# cs3.net
KiCad netlist of a schematic drawn in EAGLE
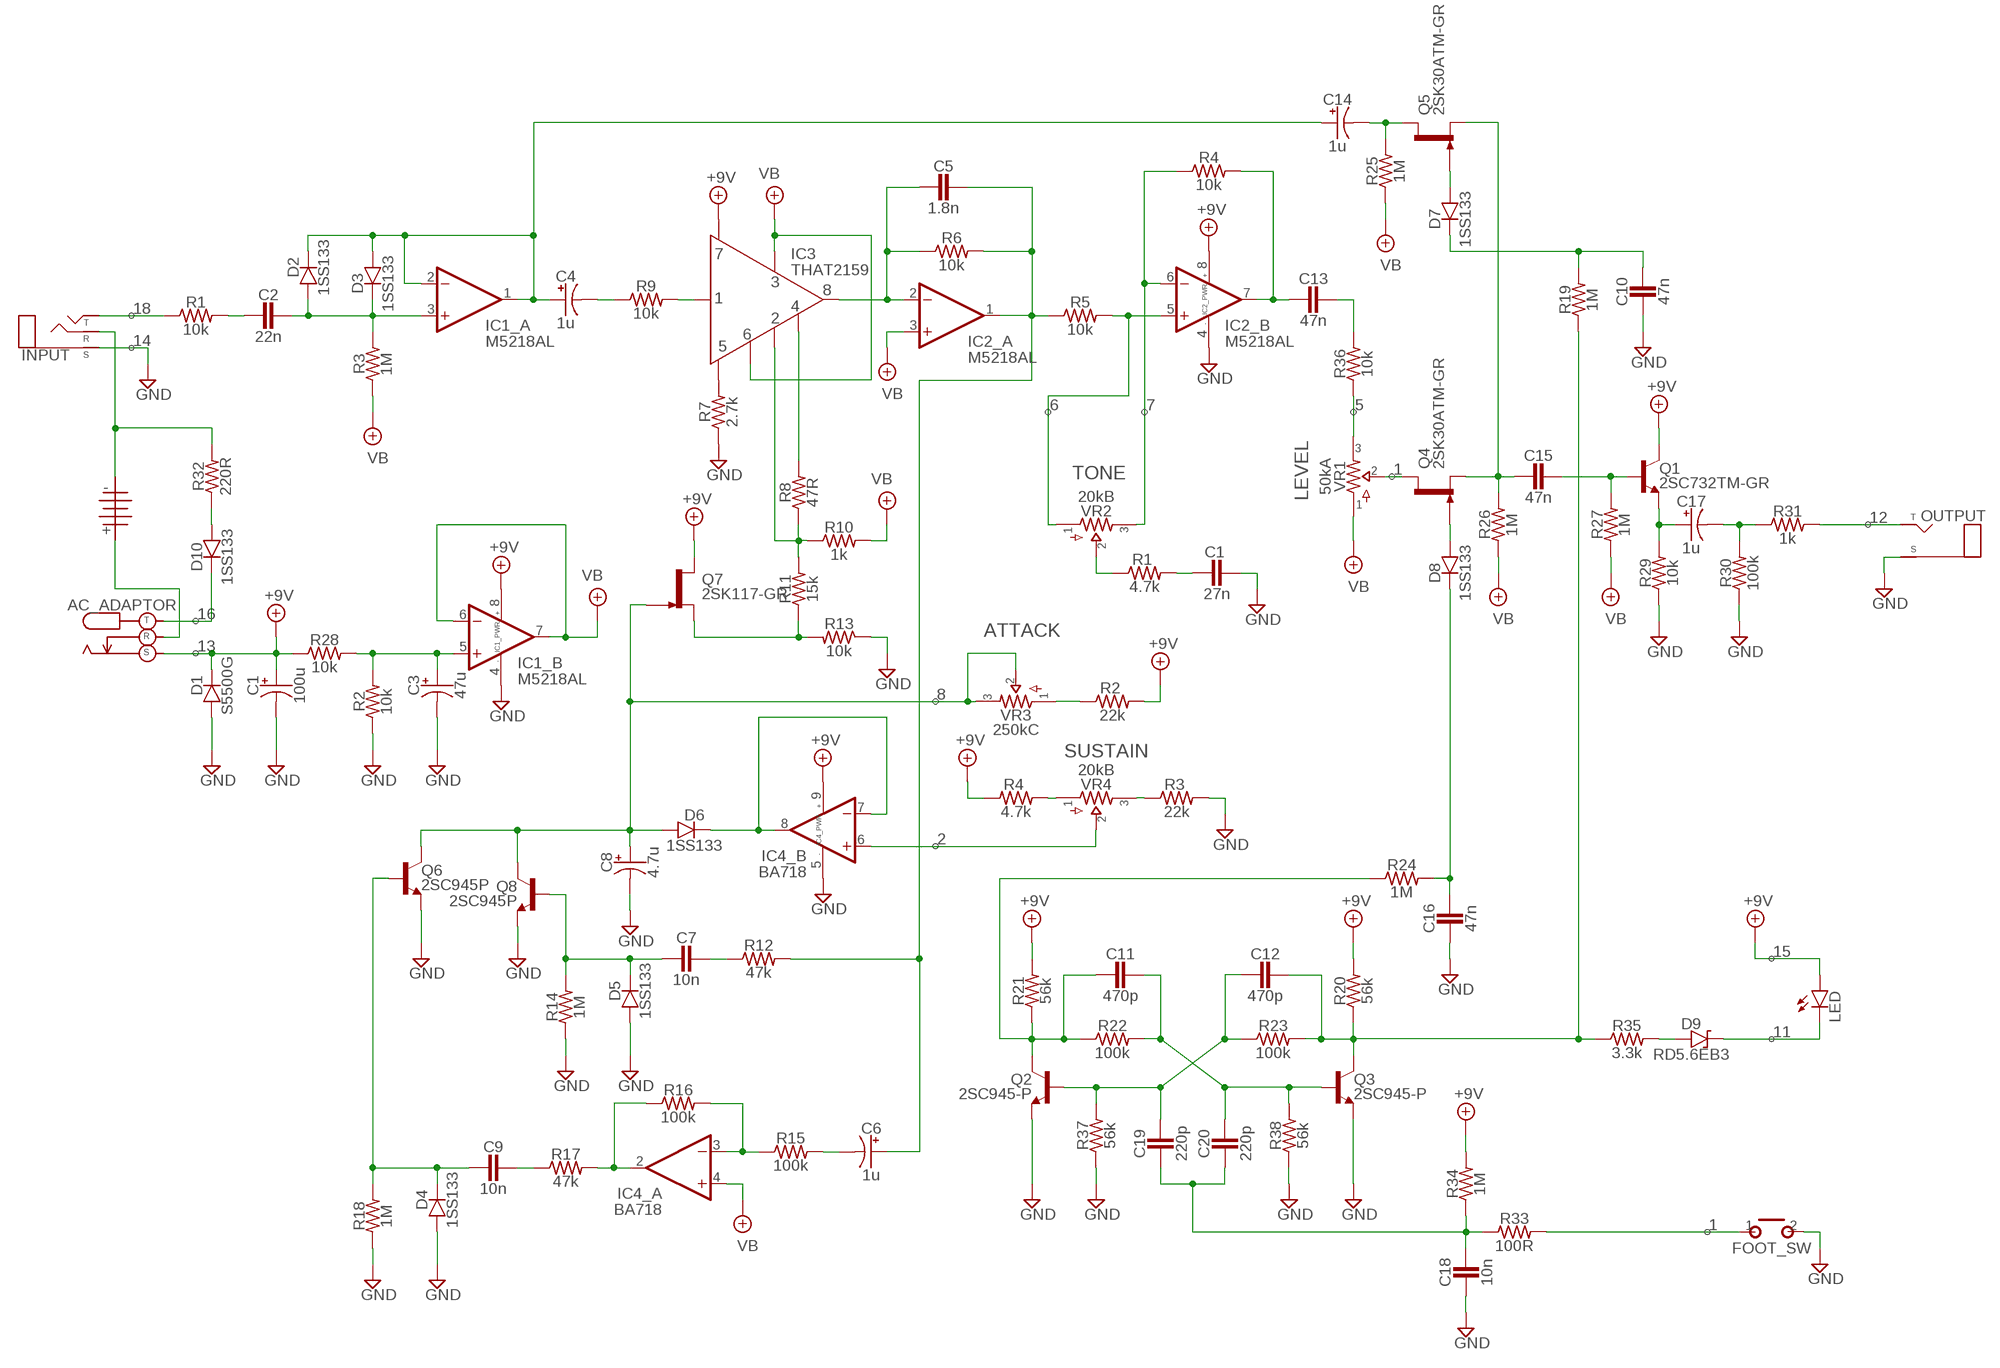
[diagram p0: schematic, sheet 1]

(export (version "E")
  (design (tool "Eeschema 10.0.6"))
  (components
    (comp (ref "1101")
      (value "BATTERY")
      (footprint "eagle-import:TWO_PADS")
      (libsource (lib "eagle-import") (part "BATTERY"))
    )
    (comp (ref "AC_ADAPTOR")
      (value "DC_KOBICONN")
      (footprint "eagle-import:DC_KOBICONN")
      (libsource (lib "eagle-import") (part "DC_KOBICONN"))
    )
    (comp (ref "C1")
      (value "100u")
      (footprint "eagle-import:040_020")
      (libsource (lib "eagle-import") (part "0400"))
    )
    (comp (ref "C1 ")
      (value "27n")
      (footprint "eagle-import:BOX_SMALL")
      (libsource (lib "eagle-import") (part "CER/FILMBOX.1"))
    )
    (comp (ref "C2")
      (value "22n")
      (footprint "eagle-import:BOX_SMALL")
      (libsource (lib "eagle-import") (part "CER/FILMBOX.1"))
    )
    (comp (ref "C3")
      (value "47u")
      (footprint "eagle-import:040_020")
      (libsource (lib "eagle-import") (part "0400"))
    )
    (comp (ref "C4")
      (value "1u")
      (footprint "eagle-import:040_020")
      (libsource (lib "eagle-import") (part "0400"))
    )
    (comp (ref "C5")
      (value "1.8n")
      (footprint "eagle-import:BOX_SMALL")
      (libsource (lib "eagle-import") (part "CER/FILMBOX.1"))
    )
    (comp (ref "C6")
      (value "1u")
      (footprint "eagle-import:040_020")
      (libsource (lib "eagle-import") (part "0400"))
    )
    (comp (ref "C7")
      (value "10n")
      (footprint "eagle-import:BOX_SMALL")
      (libsource (lib "eagle-import") (part "CER/FILMBOX.1"))
    )
    (comp (ref "C8")
      (value "4.7u")
      (footprint "eagle-import:040_020")
      (libsource (lib "eagle-import") (part "0400"))
    )
    (comp (ref "C9")
      (value "10n")
      (footprint "eagle-import:BOX_SMALL")
      (libsource (lib "eagle-import") (part "CER/FILMBOX.1"))
    )
    (comp (ref "C10")
      (value "47n")
      (footprint "eagle-import:BOX_SMALL")
      (libsource (lib "eagle-import") (part "CER/FILMBOX.1"))
    )
    (comp (ref "C11")
      (value "470p")
      (footprint "eagle-import:BOX_SMALL")
      (libsource (lib "eagle-import") (part "CER/FILMBOX.1"))
    )
    (comp (ref "C12")
      (value "470p")
      (footprint "eagle-import:BOX_SMALL")
      (libsource (lib "eagle-import") (part "CER/FILMBOX.1"))
    )
    (comp (ref "C13")
      (value "47n")
      (footprint "eagle-import:BOX_SMALL")
      (libsource (lib "eagle-import") (part "CER/FILMBOX.1"))
    )
    (comp (ref "C14")
      (value "1u")
      (footprint "eagle-import:040_020")
      (libsource (lib "eagle-import") (part "0400"))
    )
    (comp (ref "C15")
      (value "47n")
      (footprint "eagle-import:BOX_SMALL")
      (libsource (lib "eagle-import") (part "CER/FILMBOX.1"))
    )
    (comp (ref "C16")
      (value "47n")
      (footprint "eagle-import:BOX_SMALL")
      (libsource (lib "eagle-import") (part "CER/FILMBOX.1"))
    )
    (comp (ref "C17")
      (value "1u")
      (footprint "eagle-import:040_020")
      (libsource (lib "eagle-import") (part "0400"))
    )
    (comp (ref "C18")
      (value "10n")
      (footprint "eagle-import:BOX_SMALL")
      (libsource (lib "eagle-import") (part "CER/FILMBOX.1"))
    )
    (comp (ref "C19")
      (value "220p")
      (footprint "eagle-import:BOX_SMALL")
      (libsource (lib "eagle-import") (part "CER/FILMBOX.1"))
    )
    (comp (ref "C20")
      (value "220p")
      (footprint "eagle-import:BOX_SMALL")
      (libsource (lib "eagle-import") (part "CER/FILMBOX.1"))
    )
    (comp (ref "D1")
      (value "S5500G")
      (footprint "eagle-import:DO35-2")
      (libsource (lib "eagle-import") (part "DO35.2"))
    )
    (comp (ref "D2")
      (value "1SS133")
      (footprint "eagle-import:DO35-2")
      (libsource (lib "eagle-import") (part "DO35.2"))
    )
    (comp (ref "D3")
      (value "1SS133")
      (footprint "eagle-import:DO35-2")
      (libsource (lib "eagle-import") (part "DO35.2"))
    )
    (comp (ref "D4")
      (value "1SS133")
      (footprint "eagle-import:DO35-2")
      (libsource (lib "eagle-import") (part "DO35.2"))
    )
    (comp (ref "D5")
      (value "1SS133")
      (footprint "eagle-import:DO35-2")
      (libsource (lib "eagle-import") (part "DO35.2"))
    )
    (comp (ref "D6")
      (value "1SS133")
      (footprint "eagle-import:DO35-2")
      (libsource (lib "eagle-import") (part "DO35.2"))
    )
    (comp (ref "D7")
      (value "1SS133")
      (footprint "eagle-import:DO35-2")
      (libsource (lib "eagle-import") (part "DO35.2"))
    )
    (comp (ref "D8")
      (value "1SS133")
      (footprint "eagle-import:DO35-2")
      (libsource (lib "eagle-import") (part "DO35.2"))
    )
    (comp (ref "D9")
      (value "RD5.6EB3")
      (footprint "eagle-import:DO41-2")
      (libsource (lib "eagle-import") (part "ZENER.2"))
    )
    (comp (ref "D10")
      (value "1SS133")
      (footprint "eagle-import:DO35-2")
      (libsource (lib "eagle-import") (part "DO35.2"))
    )
    (comp (ref "FOOT_SW")
      (value "MOMENTARY")
      (footprint "eagle-import:SPST")
      (libsource (lib "eagle-import") (part "MOMENTARY"))
    )
    (comp (ref "IC1")
      (value "M5218AL")
      (footprint "eagle-import:DIL0")
      (libsource (lib "eagle-import") (part "DUALTH"))
    )
    (comp (ref "IC2")
      (value "M5218AL")
      (footprint "eagle-import:DIL0")
      (libsource (lib "eagle-import") (part "DUALTH"))
    )
    (comp (ref "IC3")
      (value "THAT2159")
      (footprint "eagle-import:SIL8")
      (libsource (lib "eagle-import") (part "THAT2181C"))
    )
    (comp (ref "IC4")
      (value "BA718")
      (footprint "eagle-import:SIL09")
      (libsource (lib "eagle-import") (part "DUAL"))
    )
    (comp (ref "INPUT")
      (value "STEREO3PADS")
      (footprint "eagle-import:THREEPADS")
      (libsource (lib "eagle-import") (part "STEREO3PADS"))
    )
    (comp (ref "LED")
      (value "LED")
      (footprint "eagle-import:3MM_D")
      (libsource (lib "eagle-import") (part "LED"))
    )
    (comp (ref "OUTPUT")
      (value "MONO")
      (footprint "eagle-import:TWO_PADS")
      (libsource (lib "eagle-import") (part "MONO"))
    )
    (comp (ref "Q1")
      (value "2SC732TM-GR")
      (footprint "eagle-import:TO92-")
      (libsource (lib "eagle-import") (part "2N3904"))
    )
    (comp (ref "Q2")
      (value "2SC945-P")
      (footprint "eagle-import:TO92-")
      (libsource (lib "eagle-import") (part "2SC828A"))
    )
    (comp (ref "Q3")
      (value "2SC945-P")
      (footprint "eagle-import:TO92-")
      (libsource (lib "eagle-import") (part "2SC828A"))
    )
    (comp (ref "Q4")
      (value "2SK30ATM-GR")
      (footprint "eagle-import:TO92-")
      (libsource (lib "eagle-import") (part "2N5457"))
    )
    (comp (ref "Q5")
      (value "2SK30ATM-GR")
      (footprint "eagle-import:TO92-")
      (libsource (lib "eagle-import") (part "2N5457"))
    )
    (comp (ref "Q6")
      (value "2SC945P")
      (footprint "eagle-import:TO92-")
      (libsource (lib "eagle-import") (part "2N3904"))
    )
    (comp (ref "Q7")
      (value "2SK117-GR")
      (footprint "eagle-import:TO92-")
      (libsource (lib "eagle-import") (part "2N5457"))
    )
    (comp (ref "Q8")
      (value "2SC945P")
      (footprint "eagle-import:TO92-")
      (libsource (lib "eagle-import") (part "2N3904"))
    )
    (comp (ref "R1")
      (value "10k")
      (footprint "eagle-import:R0207_3")
      (libsource (lib "eagle-import") (part "R_.3B"))
    )
    (comp (ref "R1 ")
      (value "4.7k")
      (footprint "eagle-import:R0207_3")
      (libsource (lib "eagle-import") (part "R_.3B"))
    )
    (comp (ref "R2")
      (value "10k")
      (footprint "eagle-import:R0207_3")
      (libsource (lib "eagle-import") (part "R_.3B"))
    )
    (comp (ref "R2 ")
      (value "22k")
      (footprint "eagle-import:R0207_3")
      (libsource (lib "eagle-import") (part "R_.3B"))
    )
    (comp (ref "R3")
      (value "1M")
      (footprint "eagle-import:R0207_3")
      (libsource (lib "eagle-import") (part "R_.3B"))
    )
    (comp (ref "R3 ")
      (value "22k")
      (footprint "eagle-import:R0207_3")
      (libsource (lib "eagle-import") (part "R_.3B"))
    )
    (comp (ref "R4")
      (value "10k")
      (footprint "eagle-import:R0207_3")
      (libsource (lib "eagle-import") (part "R_.3B"))
    )
    (comp (ref "R4 ")
      (value "4.7k")
      (footprint "eagle-import:R0207_3")
      (libsource (lib "eagle-import") (part "R_.3B"))
    )
    (comp (ref "R5")
      (value "10k")
      (footprint "eagle-import:R0207_3")
      (libsource (lib "eagle-import") (part "R_.3B"))
    )
    (comp (ref "R6")
      (value "10k")
      (footprint "eagle-import:R0207_3")
      (libsource (lib "eagle-import") (part "R_.3B"))
    )
    (comp (ref "R7")
      (value "2.7k")
      (footprint "eagle-import:R0207_3")
      (libsource (lib "eagle-import") (part "R_.3B"))
    )
    (comp (ref "R8")
      (value "47R")
      (footprint "eagle-import:R0207_3")
      (libsource (lib "eagle-import") (part "R_.3B"))
    )
    (comp (ref "R9")
      (value "10k")
      (footprint "eagle-import:R0207_3")
      (libsource (lib "eagle-import") (part "R_.3B"))
    )
    (comp (ref "R10")
      (value "1k")
      (footprint "eagle-import:R0207_3")
      (libsource (lib "eagle-import") (part "R_.3B"))
    )
    (comp (ref "R11")
      (value "15k")
      (footprint "eagle-import:R0207_3")
      (libsource (lib "eagle-import") (part "R_.3B"))
    )
    (comp (ref "R12")
      (value "47k")
      (footprint "eagle-import:R0207_3")
      (libsource (lib "eagle-import") (part "R_.3B"))
    )
    (comp (ref "R13")
      (value "10k")
      (footprint "eagle-import:R0207_3")
      (libsource (lib "eagle-import") (part "R_.3B"))
    )
    (comp (ref "R14")
      (value "1M")
      (footprint "eagle-import:R0207_3")
      (libsource (lib "eagle-import") (part "R_.3B"))
    )
    (comp (ref "R15")
      (value "100k")
      (footprint "eagle-import:R0207_3")
      (libsource (lib "eagle-import") (part "R_.3B"))
    )
    (comp (ref "R16")
      (value "100k")
      (footprint "eagle-import:R0207_3")
      (libsource (lib "eagle-import") (part "R_.3B"))
    )
    (comp (ref "R17")
      (value "47k")
      (footprint "eagle-import:R0207_3")
      (libsource (lib "eagle-import") (part "R_.3B"))
    )
    (comp (ref "R18")
      (value "1M")
      (footprint "eagle-import:R0207_3")
      (libsource (lib "eagle-import") (part "R_.3B"))
    )
    (comp (ref "R19")
      (value "1M")
      (footprint "eagle-import:R0207_3")
      (libsource (lib "eagle-import") (part "R_.3B"))
    )
    (comp (ref "R20")
      (value "56k")
      (footprint "eagle-import:R0207_3")
      (libsource (lib "eagle-import") (part "R_.3B"))
    )
    (comp (ref "R21")
      (value "56k")
      (footprint "eagle-import:R0207_3")
      (libsource (lib "eagle-import") (part "R_.3B"))
    )
    (comp (ref "R22")
      (value "100k")
      (footprint "eagle-import:R0207_3")
      (libsource (lib "eagle-import") (part "R_.3B"))
    )
    (comp (ref "R23")
      (value "100k")
      (footprint "eagle-import:R0207_3")
      (libsource (lib "eagle-import") (part "R_.3B"))
    )
    (comp (ref "R24")
      (value "1M")
      (footprint "eagle-import:R0207_3")
      (libsource (lib "eagle-import") (part "R_.3B"))
    )
    (comp (ref "R25")
      (value "1M")
      (footprint "eagle-import:R0207_3")
      (libsource (lib "eagle-import") (part "R_.3B"))
    )
    (comp (ref "R26")
      (value "1M")
      (footprint "eagle-import:R0207_3")
      (libsource (lib "eagle-import") (part "R_.3B"))
    )
    (comp (ref "R27")
      (value "1M")
      (footprint "eagle-import:R0207_3")
      (libsource (lib "eagle-import") (part "R_.3B"))
    )
    (comp (ref "R28")
      (value "10k")
      (footprint "eagle-import:R0207_3")
      (libsource (lib "eagle-import") (part "R_.3B"))
    )
    (comp (ref "R29")
      (value "10k")
      (footprint "eagle-import:R0207_3")
      (libsource (lib "eagle-import") (part "R_.3B"))
    )
    (comp (ref "R30")
      (value "100k")
      (footprint "eagle-import:R0207_3")
      (libsource (lib "eagle-import") (part "R_.3B"))
    )
    (comp (ref "R31")
      (value "1k")
      (footprint "eagle-import:R0207_3")
      (libsource (lib "eagle-import") (part "R_.3B"))
    )
    (comp (ref "R32")
      (value "220R")
      (footprint "eagle-import:R0207_3")
      (libsource (lib "eagle-import") (part "R_.3B"))
    )
    (comp (ref "R33")
      (value "100R")
      (footprint "eagle-import:R0207_3")
      (libsource (lib "eagle-import") (part "R_.3B"))
    )
    (comp (ref "R34")
      (value "1M")
      (footprint "eagle-import:R0207_3")
      (libsource (lib "eagle-import") (part "R_.3B"))
    )
    (comp (ref "R35")
      (value "3.3k")
      (footprint "eagle-import:R0207_3")
      (libsource (lib "eagle-import") (part "R_.3B"))
    )
    (comp (ref "R36")
      (value "10k")
      (footprint "eagle-import:R0207_3")
      (libsource (lib "eagle-import") (part "R_.3B"))
    )
    (comp (ref "R37")
      (value "56k")
      (footprint "eagle-import:R0207_3")
      (libsource (lib "eagle-import") (part "R_.3B"))
    )
    (comp (ref "R38")
      (value "56k")
      (footprint "eagle-import:R0207_3")
      (libsource (lib "eagle-import") (part "R_.3B"))
    )
    (comp (ref "VR1")
      (value "50kA")
      (footprint "eagle-import:16MM")
      (libsource (lib "eagle-import") (part "POTS16MM"))
    )
    (comp (ref "VR2")
      (value "20kB")
      (footprint "eagle-import:16MM")
      (libsource (lib "eagle-import") (part "POTS16MM"))
    )
    (comp (ref "VR3")
      (value "250kC")
      (footprint "eagle-import:16MM")
      (libsource (lib "eagle-import") (part "POTS16MM"))
    )
    (comp (ref "VR4")
      (value "20kB")
      (footprint "eagle-import:16MM")
      (libsource (lib "eagle-import") (part "POTS16MM"))
    )
  )
  (nets
    (net (code "1") (name "+9V") (class "Default")
      (node (ref "AC_ADAPTOR") (pin "S") (pinfunction "S_S") (pintype "bidirectional"))
      (node (ref "C1") (pin "+") (pinfunction "+_+") (pintype "passive"))
      (node (ref "D1") (pin "C") (pinfunction "C_C") (pintype "passive"))
      (node (ref "IC1") (pin "8") (pinfunction "V+_8") (pintype "power_in"))
      (node (ref "IC2") (pin "8") (pinfunction "V+_8") (pintype "power_in"))
      (node (ref "IC3") (pin "7") (pinfunction "P$7_7") (pintype "bidirectional"))
      (node (ref "IC4") (pin "9") (pinfunction "V+_9") (pintype "power_in"))
      (node (ref "LED") (pin "ANODE") (pinfunction "A_ANODE") (pintype "passive"))
      (node (ref "Q1") (pin "1") (pinfunction "C_1") (pintype "passive"))
      (node (ref "Q7") (pin "3") (pinfunction "D_3") (pintype "passive"))
      (node (ref "R20") (pin "2") (pinfunction "2_2") (pintype "passive"))
      (node (ref "R21") (pin "2") (pinfunction "2_2") (pintype "passive"))
      (node (ref "R28") (pin "1") (pinfunction "1_1") (pintype "passive"))
      (node (ref "R2 ") (pin "2") (pinfunction "2_2") (pintype "passive"))
      (node (ref "R34") (pin "2") (pinfunction "2_2") (pintype "passive"))
      (node (ref "R4 ") (pin "1") (pinfunction "1_1") (pintype "passive"))
    )
    (net (code "2") (name "GND") (class "Default")
      (node (ref "C1") (pin "-") (pinfunction "-_-") (pintype "passive"))
      (node (ref "C10") (pin "2") (pinfunction "2_2") (pintype "passive"))
      (node (ref "C16") (pin "2") (pinfunction "2_2") (pintype "passive"))
      (node (ref "C18") (pin "2") (pinfunction "2_2") (pintype "passive"))
      (node (ref "C1 ") (pin "2") (pinfunction "2_2") (pintype "passive"))
      (node (ref "C3") (pin "-") (pinfunction "-_-") (pintype "passive"))
      (node (ref "C8") (pin "-") (pinfunction "-_-") (pintype "passive"))
      (node (ref "D1") (pin "A") (pinfunction "A_A") (pintype "passive"))
      (node (ref "D4") (pin "A") (pinfunction "A_A") (pintype "passive"))
      (node (ref "D5") (pin "A") (pinfunction "A_A") (pintype "passive"))
      (node (ref "FOOT_SW") (pin "2") (pinfunction "S_2") (pintype "passive"))
      (node (ref "IC1") (pin "4") (pinfunction "V-_4") (pintype "power_in"))
      (node (ref "IC2") (pin "4") (pinfunction "V-_4") (pintype "power_in"))
      (node (ref "IC4") (pin "5") (pinfunction "V-_5") (pintype "power_in"))
      (node (ref "INPUT") (pin "SLEEVE") (pinfunction "S_SLEEVE") (pintype "passive"))
      (node (ref "OUTPUT") (pin "S") (pinfunction "SLEEVE_S") (pintype "passive"))
      (node (ref "Q2") (pin "3") (pinfunction "E_3") (pintype "passive"))
      (node (ref "Q3") (pin "3") (pinfunction "E_3") (pintype "passive"))
      (node (ref "Q6") (pin "3") (pinfunction "E_3") (pintype "passive"))
      (node (ref "Q8") (pin "3") (pinfunction "E_3") (pintype "passive"))
      (node (ref "R13") (pin "1") (pinfunction "1_1") (pintype "passive"))
      (node (ref "R14") (pin "1") (pinfunction "1_1") (pintype "passive"))
      (node (ref "R18") (pin "1") (pinfunction "1_1") (pintype "passive"))
      (node (ref "R2") (pin "1") (pinfunction "1_1") (pintype "passive"))
      (node (ref "R29") (pin "1") (pinfunction "1_1") (pintype "passive"))
      (node (ref "R30") (pin "1") (pinfunction "1_1") (pintype "passive"))
      (node (ref "R37") (pin "1") (pinfunction "1_1") (pintype "passive"))
      (node (ref "R38") (pin "1") (pinfunction "1_1") (pintype "passive"))
      (node (ref "R3 ") (pin "2") (pinfunction "2_2") (pintype "passive"))
      (node (ref "R7") (pin "1") (pinfunction "1_1") (pintype "passive"))
    )
    (net (code "3") (name "Net-(1101-P$1)") (class "Default")
      (node (ref "1101") (pin "T") (pinfunction "P$1_T") (pintype "bidirectional"))
      (node (ref "AC_ADAPTOR") (pin "R") (pinfunction "R_R") (pintype "bidirectional"))
    )
    (net (code "4") (name "Net-(1101-P$2)") (class "Default")
      (node (ref "1101") (pin "S") (pinfunction "P$2_S") (pintype "bidirectional"))
      (node (ref "INPUT") (pin "RING") (pinfunction "R_RING") (pintype "passive"))
      (node (ref "R32") (pin "2") (pinfunction "2_2") (pintype "passive"))
    )
    (net (code "5") (name "Net-(AC_ADAPTOR-PadT)") (class "Default")
      (node (ref "AC_ADAPTOR") (pin "T") (pinfunction "T_T") (pintype "bidirectional"))
      (node (ref "D10") (pin "C") (pinfunction "C_C") (pintype "passive"))
    )
    (net (code "6") (name "Net-(C1 -Pad1)") (class "Default")
      (node (ref "C1 ") (pin "1") (pinfunction "1_1") (pintype "passive"))
      (node (ref "R1 ") (pin "2") (pinfunction "2_2") (pintype "passive"))
    )
    (net (code "7") (name "Net-(C2-Pad2)") (class "Default")
      (node (ref "C2") (pin "2") (pinfunction "2_2") (pintype "passive"))
      (node (ref "R1") (pin "2") (pinfunction "2_2") (pintype "passive"))
    )
    (net (code "8") (name "Net-(C4-Pad-)") (class "Default")
      (node (ref "C4") (pin "-") (pinfunction "-_-") (pintype "passive"))
      (node (ref "R9") (pin "1") (pinfunction "1_1") (pintype "passive"))
    )
    (net (code "9") (name "Net-(C6-Pad-)") (class "Default")
      (node (ref "C6") (pin "-") (pinfunction "-_-") (pintype "passive"))
      (node (ref "R15") (pin "2") (pinfunction "2_2") (pintype "passive"))
    )
    (net (code "10") (name "Net-(C7-Pad1)") (class "Default")
      (node (ref "C7") (pin "1") (pinfunction "1_1") (pintype "passive"))
      (node (ref "R12") (pin "1") (pinfunction "1_1") (pintype "passive"))
    )
    (net (code "11") (name "Net-(C9-Pad1)") (class "Default")
      (node (ref "C9") (pin "1") (pinfunction "1_1") (pintype "passive"))
      (node (ref "R17") (pin "1") (pinfunction "1_1") (pintype "passive"))
    )
    (net (code "12") (name "Net-(C10-Pad1)") (class "Default")
      (node (ref "C10") (pin "1") (pinfunction "1_1") (pintype "passive"))
      (node (ref "D7") (pin "C") (pinfunction "C_C") (pintype "passive"))
      (node (ref "R19") (pin "2") (pinfunction "2_2") (pintype "passive"))
    )
    (net (code "13") (name "Net-(C13-Pad1)") (class "Default")
      (node (ref "C13") (pin "1") (pinfunction "1_1") (pintype "passive"))
      (node (ref "R36") (pin "2") (pinfunction "2_2") (pintype "passive"))
    )
    (net (code "14") (name "Net-(C16-Pad1)") (class "Default")
      (node (ref "C16") (pin "1") (pinfunction "1_1") (pintype "passive"))
      (node (ref "D8") (pin "C") (pinfunction "C_C") (pintype "passive"))
      (node (ref "R24") (pin "2") (pinfunction "2_2") (pintype "passive"))
    )
    (net (code "15") (name "Net-(C17-Pad-)") (class "Default")
      (node (ref "C17") (pin "-") (pinfunction "-_-") (pintype "passive"))
      (node (ref "R30") (pin "2") (pinfunction "2_2") (pintype "passive"))
      (node (ref "R31") (pin "1") (pinfunction "1_1") (pintype "passive"))
    )
    (net (code "16") (name "Net-(C18-Pad1)") (class "Default")
      (node (ref "C18") (pin "1") (pinfunction "1_1") (pintype "passive"))
      (node (ref "C19") (pin "2") (pinfunction "2_2") (pintype "passive"))
      (node (ref "C20") (pin "2") (pinfunction "2_2") (pintype "passive"))
      (node (ref "R33") (pin "1") (pinfunction "1_1") (pintype "passive"))
      (node (ref "R34") (pin "1") (pinfunction "1_1") (pintype "passive"))
    )
    (net (code "17") (name "Net-(D9-PadA)") (class "Default")
      (node (ref "D9") (pin "A") (pinfunction "A_A") (pintype "passive"))
      (node (ref "R35") (pin "2") (pinfunction "2_2") (pintype "passive"))
    )
    (net (code "18") (name "Net-(D10-PadA)") (class "Default")
      (node (ref "D10") (pin "A") (pinfunction "A_A") (pintype "passive"))
      (node (ref "R32") (pin "1") (pinfunction "1_1") (pintype "passive"))
    )
    (net (code "19") (name "Net-(FOOT_SW-P)") (class "Default")
      (node (ref "FOOT_SW") (pin "1") (pinfunction "P_1") (pintype "passive"))
      (node (ref "R33") (pin "2") (pinfunction "2_2") (pintype "passive"))
    )
    (net (code "20") (name "Net-(IC1A-+IN)") (class "Default")
      (node (ref "C2") (pin "1") (pinfunction "1_1") (pintype "passive"))
      (node (ref "D2") (pin "A") (pinfunction "A_A") (pintype "passive"))
      (node (ref "D3") (pin "C") (pinfunction "C_C") (pintype "passive"))
      (node (ref "IC1") (pin "3") (pinfunction "+IN_3") (pintype "input"))
      (node (ref "R3") (pin "2") (pinfunction "2_2") (pintype "passive"))
    )
    (net (code "21") (name "Net-(IC1A--IN)") (class "Default")
      (node (ref "C14") (pin "+") (pinfunction "+_+") (pintype "passive"))
      (node (ref "C4") (pin "+") (pinfunction "+_+") (pintype "passive"))
      (node (ref "D2") (pin "C") (pinfunction "C_C") (pintype "passive"))
      (node (ref "D3") (pin "A") (pinfunction "A_A") (pintype "passive"))
      (node (ref "IC1") (pin "1") (pinfunction "OUT_1") (pintype "output"))
      (node (ref "IC1") (pin "2") (pinfunction "-IN_2") (pintype "input"))
    )
    (net (code "22") (name "Net-(IC1B-+IN)") (class "Default")
      (node (ref "C3") (pin "+") (pinfunction "+_+") (pintype "passive"))
      (node (ref "IC1") (pin "5") (pinfunction "+IN_5") (pintype "input"))
      (node (ref "R2") (pin "2") (pinfunction "2_2") (pintype "passive"))
      (node (ref "R28") (pin "2") (pinfunction "2_2") (pintype "passive"))
    )
    (net (code "23") (name "Net-(IC2A--IN)") (class "Default")
      (node (ref "C5") (pin "2") (pinfunction "2_2") (pintype "passive"))
      (node (ref "IC2") (pin "2") (pinfunction "-IN_2") (pintype "input"))
      (node (ref "IC3") (pin "8") (pinfunction "P$8_8") (pintype "bidirectional"))
      (node (ref "R6") (pin "1") (pinfunction "1_1") (pintype "passive"))
    )
    (net (code "24") (name "Net-(IC2A-OUT)") (class "Default")
      (node (ref "C5") (pin "1") (pinfunction "1_1") (pintype "passive"))
      (node (ref "C6") (pin "+") (pinfunction "+_+") (pintype "passive"))
      (node (ref "IC2") (pin "1") (pinfunction "OUT_1") (pintype "output"))
      (node (ref "R12") (pin "2") (pinfunction "2_2") (pintype "passive"))
      (node (ref "R5") (pin "1") (pinfunction "1_1") (pintype "passive"))
      (node (ref "R6") (pin "2") (pinfunction "2_2") (pintype "passive"))
    )
    (net (code "25") (name "Net-(IC2B-+IN)") (class "Default")
      (node (ref "IC2") (pin "5") (pinfunction "+IN_5") (pintype "input"))
      (node (ref "R5") (pin "2") (pinfunction "2_2") (pintype "passive"))
      (node (ref "VR2") (pin "1") (pinfunction "1_1") (pintype "passive"))
    )
    (net (code "26") (name "Net-(IC2B--IN)") (class "Default")
      (node (ref "IC2") (pin "6") (pinfunction "-IN_6") (pintype "input"))
      (node (ref "R4") (pin "1") (pinfunction "1_1") (pintype "passive"))
      (node (ref "VR2") (pin "3") (pinfunction "3_3") (pintype "passive"))
    )
    (net (code "27") (name "Net-(IC2B-OUT)") (class "Default")
      (node (ref "C13") (pin "2") (pinfunction "2_2") (pintype "passive"))
      (node (ref "IC2") (pin "7") (pinfunction "OUT_7") (pintype "output"))
      (node (ref "R4") (pin "2") (pinfunction "2_2") (pintype "passive"))
    )
    (net (code "28") (name "Net-(IC3-P$1)") (class "Default")
      (node (ref "IC3") (pin "1") (pinfunction "P$1_1") (pintype "bidirectional"))
      (node (ref "R9") (pin "2") (pinfunction "2_2") (pintype "passive"))
    )
    (net (code "29") (name "Net-(IC3-P$2)") (class "Default")
      (node (ref "IC3") (pin "2") (pinfunction "P$2_2") (pintype "bidirectional"))
      (node (ref "R10") (pin "1") (pinfunction "1_1") (pintype "passive"))
      (node (ref "R11") (pin "2") (pinfunction "2_2") (pintype "passive"))
      (node (ref "R8") (pin "1") (pinfunction "1_1") (pintype "passive"))
    )
    (net (code "30") (name "Net-(IC3-P$4)") (class "Default")
      (node (ref "IC3") (pin "4") (pinfunction "P$4_4") (pintype "bidirectional"))
      (node (ref "R8") (pin "2") (pinfunction "2_2") (pintype "passive"))
    )
    (net (code "31") (name "Net-(IC3-P$5)") (class "Default")
      (node (ref "IC3") (pin "5") (pinfunction "P$5_5") (pintype "bidirectional"))
      (node (ref "R7") (pin "2") (pinfunction "2_2") (pintype "passive"))
    )
    (net (code "32") (name "Net-(IC4A--IN)") (class "Default")
      (node (ref "IC4") (pin "3") (pinfunction "-IN_3") (pintype "input"))
      (node (ref "R15") (pin "1") (pinfunction "1_1") (pintype "passive"))
      (node (ref "R16") (pin "2") (pinfunction "2_2") (pintype "passive"))
    )
    (net (code "33") (name "Net-(IC4A-OUT)") (class "Default")
      (node (ref "IC4") (pin "2") (pinfunction "OUT_2") (pintype "output"))
      (node (ref "R16") (pin "1") (pinfunction "1_1") (pintype "passive"))
      (node (ref "R17") (pin "2") (pinfunction "2_2") (pintype "passive"))
    )
    (net (code "34") (name "Net-(IC4B-+IN)") (class "Default")
      (node (ref "IC4") (pin "6") (pinfunction "+IN_6") (pintype "input"))
      (node (ref "VR4") (pin "2") (pinfunction "2_2") (pintype "passive"))
    )
    (net (code "35") (name "Net-(IC4B--IN)") (class "Default")
      (node (ref "D6") (pin "C") (pinfunction "C_C") (pintype "passive"))
      (node (ref "IC4") (pin "7") (pinfunction "-IN_7") (pintype "input"))
      (node (ref "IC4") (pin "8") (pinfunction "OUT_8") (pintype "output"))
    )
    (net (code "36") (name "Net-(INPUT-T)") (class "Default")
      (node (ref "INPUT") (pin "TIP") (pinfunction "T_TIP") (pintype "passive"))
      (node (ref "R1") (pin "1") (pinfunction "1_1") (pintype "passive"))
    )
    (net (code "37") (name "Net-(LED-C)") (class "Default")
      (node (ref "D9") (pin "C") (pinfunction "C_C") (pintype "passive"))
      (node (ref "LED") (pin "P$1") (pinfunction "C_P$1") (pintype "passive"))
    )
    (net (code "38") (name "Net-(OUTPUT-TIP)") (class "Default")
      (node (ref "OUTPUT") (pin "T") (pinfunction "TIP_T") (pintype "passive"))
      (node (ref "R31") (pin "2") (pinfunction "2_2") (pintype "passive"))
    )
    (net (code "39") (name "Net-(Q1-B)") (class "Default")
      (node (ref "C15") (pin "1") (pinfunction "1_1") (pintype "passive"))
      (node (ref "Q1") (pin "2") (pinfunction "B_2") (pintype "passive"))
      (node (ref "R27") (pin "2") (pinfunction "2_2") (pintype "passive"))
    )
    (net (code "40") (name "Net-(Q1-E)") (class "Default")
      (node (ref "C17") (pin "+") (pinfunction "+_+") (pintype "passive"))
      (node (ref "Q1") (pin "3") (pinfunction "E_3") (pintype "passive"))
      (node (ref "R29") (pin "2") (pinfunction "2_2") (pintype "passive"))
    )
    (net (code "41") (name "Net-(Q2-B)") (class "Default")
      (node (ref "C12") (pin "2") (pinfunction "2_2") (pintype "passive"))
      (node (ref "C19") (pin "1") (pinfunction "1_1") (pintype "passive"))
      (node (ref "Q2") (pin "1") (pinfunction "B_1") (pintype "passive"))
      (node (ref "R23") (pin "1") (pinfunction "1_1") (pintype "passive"))
      (node (ref "R37") (pin "2") (pinfunction "2_2") (pintype "passive"))
    )
    (net (code "42") (name "Net-(Q2-C)") (class "Default")
      (node (ref "C11") (pin "2") (pinfunction "2_2") (pintype "passive"))
      (node (ref "Q2") (pin "2") (pinfunction "C_2") (pintype "passive"))
      (node (ref "R21") (pin "1") (pinfunction "1_1") (pintype "passive"))
      (node (ref "R22") (pin "1") (pinfunction "1_1") (pintype "passive"))
      (node (ref "R24") (pin "1") (pinfunction "1_1") (pintype "passive"))
    )
    (net (code "43") (name "Net-(Q3-B)") (class "Default")
      (node (ref "C11") (pin "1") (pinfunction "1_1") (pintype "passive"))
      (node (ref "C20") (pin "1") (pinfunction "1_1") (pintype "passive"))
      (node (ref "Q3") (pin "1") (pinfunction "B_1") (pintype "passive"))
      (node (ref "R22") (pin "2") (pinfunction "2_2") (pintype "passive"))
      (node (ref "R38") (pin "2") (pinfunction "2_2") (pintype "passive"))
    )
    (net (code "44") (name "Net-(Q3-C)") (class "Default")
      (node (ref "C12") (pin "1") (pinfunction "1_1") (pintype "passive"))
      (node (ref "Q3") (pin "2") (pinfunction "C_2") (pintype "passive"))
      (node (ref "R19") (pin "1") (pinfunction "1_1") (pintype "passive"))
      (node (ref "R20") (pin "1") (pinfunction "1_1") (pintype "passive"))
      (node (ref "R23") (pin "2") (pinfunction "2_2") (pintype "passive"))
      (node (ref "R35") (pin "1") (pinfunction "1_1") (pintype "passive"))
    )
    (net (code "45") (name "Net-(Q4-D)") (class "Default")
      (node (ref "Q4") (pin "3") (pinfunction "D_3") (pintype "passive"))
      (node (ref "VR1") (pin "2") (pinfunction "2_2") (pintype "passive"))
    )
    (net (code "46") (name "Net-(Q4-G)") (class "Default")
      (node (ref "D8") (pin "A") (pinfunction "A_A") (pintype "passive"))
      (node (ref "Q4") (pin "1") (pinfunction "G_1") (pintype "passive"))
    )
    (net (code "47") (name "Net-(Q4-S)") (class "Default")
      (node (ref "C15") (pin "2") (pinfunction "2_2") (pintype "passive"))
      (node (ref "Q4") (pin "2") (pinfunction "S_2") (pintype "passive"))
      (node (ref "Q5") (pin "2") (pinfunction "S_2") (pintype "passive"))
      (node (ref "R26") (pin "2") (pinfunction "2_2") (pintype "passive"))
    )
    (net (code "48") (name "Net-(Q5-D)") (class "Default")
      (node (ref "C14") (pin "-") (pinfunction "-_-") (pintype "passive"))
      (node (ref "Q5") (pin "3") (pinfunction "D_3") (pintype "passive"))
      (node (ref "R25") (pin "2") (pinfunction "2_2") (pintype "passive"))
    )
    (net (code "49") (name "Net-(Q5-G)") (class "Default")
      (node (ref "D7") (pin "A") (pinfunction "A_A") (pintype "passive"))
      (node (ref "Q5") (pin "1") (pinfunction "G_1") (pintype "passive"))
    )
    (net (code "50") (name "Net-(Q6-B)") (class "Default")
      (node (ref "C9") (pin "2") (pinfunction "2_2") (pintype "passive"))
      (node (ref "D4") (pin "C") (pinfunction "C_C") (pintype "passive"))
      (node (ref "Q6") (pin "2") (pinfunction "B_2") (pintype "passive"))
      (node (ref "R18") (pin "2") (pinfunction "2_2") (pintype "passive"))
    )
    (net (code "51") (name "Net-(Q6-C)") (class "Default")
      (node (ref "C8") (pin "+") (pinfunction "+_+") (pintype "passive"))
      (node (ref "D6") (pin "A") (pinfunction "A_A") (pintype "passive"))
      (node (ref "Q6") (pin "1") (pinfunction "C_1") (pintype "passive"))
      (node (ref "Q7") (pin "1") (pinfunction "G_1") (pintype "passive"))
      (node (ref "Q8") (pin "1") (pinfunction "C_1") (pintype "passive"))
      (node (ref "VR3") (pin "2") (pinfunction "2_2") (pintype "passive"))
      (node (ref "VR3") (pin "3") (pinfunction "3_3") (pintype "passive"))
    )
    (net (code "52") (name "Net-(Q7-S)") (class "Default")
      (node (ref "Q7") (pin "2") (pinfunction "S_2") (pintype "passive"))
      (node (ref "R11") (pin "1") (pinfunction "1_1") (pintype "passive"))
      (node (ref "R13") (pin "2") (pinfunction "2_2") (pintype "passive"))
    )
    (net (code "53") (name "Net-(Q8-B)") (class "Default")
      (node (ref "C7") (pin "2") (pinfunction "2_2") (pintype "passive"))
      (node (ref "D5") (pin "C") (pinfunction "C_C") (pintype "passive"))
      (node (ref "Q8") (pin "2") (pinfunction "B_2") (pintype "passive"))
      (node (ref "R14") (pin "2") (pinfunction "2_2") (pintype "passive"))
    )
    (net (code "54") (name "Net-(R1 -Pad1)") (class "Default")
      (node (ref "R1 ") (pin "1") (pinfunction "1_1") (pintype "passive"))
      (node (ref "VR2") (pin "2") (pinfunction "2_2") (pintype "passive"))
    )
    (net (code "55") (name "Net-(R2 -Pad1)") (class "Default")
      (node (ref "R2 ") (pin "1") (pinfunction "1_1") (pintype "passive"))
      (node (ref "VR3") (pin "1") (pinfunction "1_1") (pintype "passive"))
    )
    (net (code "56") (name "Net-(R3 -Pad1)") (class "Default")
      (node (ref "R3 ") (pin "1") (pinfunction "1_1") (pintype "passive"))
      (node (ref "VR4") (pin "3") (pinfunction "3_3") (pintype "passive"))
    )
    (net (code "57") (name "Net-(R4 -Pad2)") (class "Default")
      (node (ref "R4 ") (pin "2") (pinfunction "2_2") (pintype "passive"))
      (node (ref "VR4") (pin "1") (pinfunction "1_1") (pintype "passive"))
    )
    (net (code "58") (name "Net-(R36-Pad1)") (class "Default")
      (node (ref "R36") (pin "1") (pinfunction "1_1") (pintype "passive"))
      (node (ref "VR1") (pin "3") (pinfunction "3_3") (pintype "passive"))
    )
    (net (code "59") (name "VB") (class "Default")
      (node (ref "IC1") (pin "6") (pinfunction "-IN_6") (pintype "input"))
      (node (ref "IC1") (pin "7") (pinfunction "OUT_7") (pintype "output"))
      (node (ref "IC2") (pin "3") (pinfunction "+IN_3") (pintype "input"))
      (node (ref "IC3") (pin "3") (pinfunction "P$3_3") (pintype "bidirectional"))
      (node (ref "IC3") (pin "6") (pinfunction "P$6_6") (pintype "bidirectional"))
      (node (ref "IC4") (pin "4") (pinfunction "+IN_4") (pintype "input"))
      (node (ref "R10") (pin "2") (pinfunction "2_2") (pintype "passive"))
      (node (ref "R25") (pin "1") (pinfunction "1_1") (pintype "passive"))
      (node (ref "R26") (pin "1") (pinfunction "1_1") (pintype "passive"))
      (node (ref "R27") (pin "1") (pinfunction "1_1") (pintype "passive"))
      (node (ref "R3") (pin "1") (pinfunction "1_1") (pintype "passive"))
      (node (ref "VR1") (pin "1") (pinfunction "1_1") (pintype "passive"))
    )
  )
)
